# USB_To_Serial.net
KiCad netlist of a schematic drawn in Altium Designer
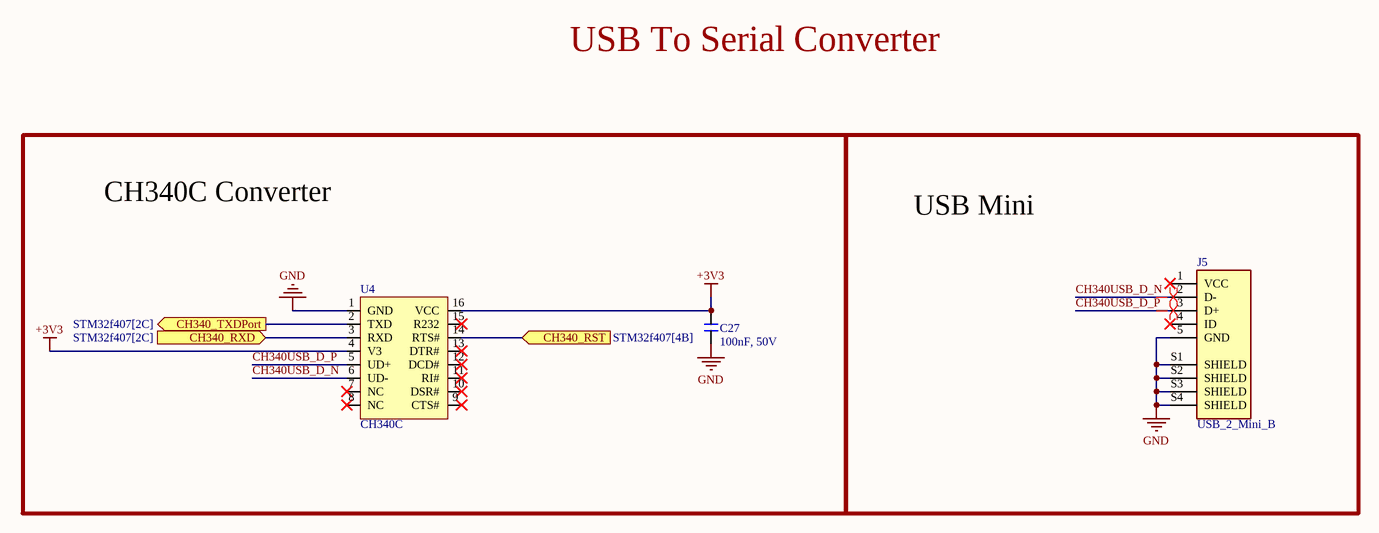
[diagram p0: USB_To_Serial.SchDoc]

(export (version "E")
  (design (tool "Eeschema 10.0.6"))
  (components
    (comp (ref "C27")
      (value "100nF, 50V")
      (footprint "Capacitor_0805")
      (description "Multilayer Ceramic Capacitor, 0.1 uF, 50 V, ï¿½ 10%, X7R, 0805 [2012 Metric]")
      (fields
        (field (name "MANUFACTURER") "Samsung")
        (field (name "MANUFACTURER PART NUMBER") "CL21B104KBCNNNC")
      )
      (libsource (lib "Schematics_Library_Hanif") (part "Cap_100nF_0805"))
    )
    (comp (ref "J5")
      (value "USB_2_Mini_B")
      (footprint "USB_2_Mini")
      (description "Conn Mini USB 2.0 Type B RCP 5 POS 0.8mm Solder RA SMD 5 Terminal 1 Port")
      (fields
        (field (name "MANUFACTURER") "EDAC")
        (field (name "MANUFACTURER PART NUMBER") "690-005-299-043")
      )
      (libsource (lib "Schematics_Library_Hanif") (part "USB2_Mini_690-B_005-299-043"))
    )
    (comp (ref "U4")
      (value "CH340C")
      (footprint "SOIC-16")
      (description "2Mbps Transceiver USB 2.0 SOP-16 USB Converters ROHS")
      (fields (field (name "MANUFACTURER") "WCH(Jiangsu Qin Heng)"))
      (libsource (lib "Schematics_Library_Hanif") (part "IC_USB_To_SerialCH340C"))
    )
  )
  (nets
    (net (code "1") (name "+3V3") (class "Default")
      (node (ref "C27") (pin "2") (pinfunction "2_2") (pintype "passive"))
      (node (ref "U4") (pin "16") (pinfunction "VCC_16") (pintype "passive"))
      (node (ref "U4") (pin "4") (pinfunction "V3_4") (pintype "passive"))
    )
    (net (code "2") (name "/CH340USB_D_N") (class "Default")
      (node (ref "J5") (pin "2") (pinfunction "D-_2") (pintype "passive"))
      (node (ref "U4") (pin "6") (pinfunction "UD-_6") (pintype "passive"))
    )
    (net (code "3") (name "/CH340USB_D_P") (class "Default")
      (node (ref "J5") (pin "3") (pinfunction "D+_3") (pintype "passive"))
      (node (ref "U4") (pin "5") (pinfunction "UD+_5") (pintype "passive"))
    )
    (net (code "4") (name "/CH340_RST") (class "Default")
      (node (ref "U4") (pin "14") (pinfunction "RTS#_14") (pintype "passive"))
    )
    (net (code "5") (name "/CH340_RXD") (class "Default")
      (node (ref "U4") (pin "3") (pinfunction "RXD_3") (pintype "passive"))
    )
    (net (code "6") (name "/CH340_TXDPort") (class "Default")
      (node (ref "U4") (pin "2") (pinfunction "TXD_2") (pintype "passive"))
    )
    (net (code "7") (name "GND") (class "Default")
      (node (ref "C27") (pin "1") (pinfunction "1_1") (pintype "passive"))
      (node (ref "J5") (pin "5") (pinfunction "GND_5") (pintype "passive"))
      (node (ref "J5") (pin "S1") (pinfunction "SHIELD_S1") (pintype "passive"))
      (node (ref "J5") (pin "S2") (pinfunction "SHIELD_S2") (pintype "passive"))
      (node (ref "J5") (pin "S3") (pinfunction "SHIELD_S3") (pintype "passive"))
      (node (ref "J5") (pin "S4") (pinfunction "SHIELD_S4") (pintype "passive"))
      (node (ref "U4") (pin "1") (pinfunction "GND_1") (pintype "passive"))
    )
    (net (code "8") (name "unconnected-(J5-ID-Pad4)") (class "Default")
      (node (ref "J5") (pin "4") (pinfunction "ID_4") (pintype "passive+no_connect"))
    )
    (net (code "9") (name "unconnected-(J5-VCC-Pad1)") (class "Default")
      (node (ref "J5") (pin "1") (pinfunction "VCC_1") (pintype "passive+no_connect"))
    )
    (net (code "10") (name "unconnected-(U4-CTS#-Pad9)") (class "Default")
      (node (ref "U4") (pin "9") (pinfunction "CTS#_9") (pintype "passive+no_connect"))
    )
    (net (code "11") (name "unconnected-(U4-DCD#-Pad12)") (class "Default")
      (node (ref "U4") (pin "12") (pinfunction "DCD#_12") (pintype "passive+no_connect"))
    )
    (net (code "12") (name "unconnected-(U4-DSR#-Pad10)") (class "Default")
      (node (ref "U4") (pin "10") (pinfunction "DSR#_10") (pintype "passive+no_connect"))
    )
    (net (code "13") (name "unconnected-(U4-DTR#-Pad13)") (class "Default")
      (node (ref "U4") (pin "13") (pinfunction "DTR#_13") (pintype "passive+no_connect"))
    )
    (net (code "14") (name "unconnected-(U4-NC-Pad7)") (class "Default")
      (node (ref "U4") (pin "7") (pinfunction "NC_7") (pintype "passive+no_connect"))
    )
    (net (code "15") (name "unconnected-(U4-NC-Pad8)") (class "Default")
      (node (ref "U4") (pin "8") (pinfunction "NC_8") (pintype "passive+no_connect"))
    )
    (net (code "16") (name "unconnected-(U4-R232-Pad15)") (class "Default")
      (node (ref "U4") (pin "15") (pinfunction "R232_15") (pintype "passive+no_connect"))
    )
    (net (code "17") (name "unconnected-(U4-RI#-Pad11)") (class "Default")
      (node (ref "U4") (pin "11") (pinfunction "RI#_11") (pintype "passive+no_connect"))
    )
  )
)
